# DS18B20.net
KiCad netlist of a schematic drawn in Altium Designer
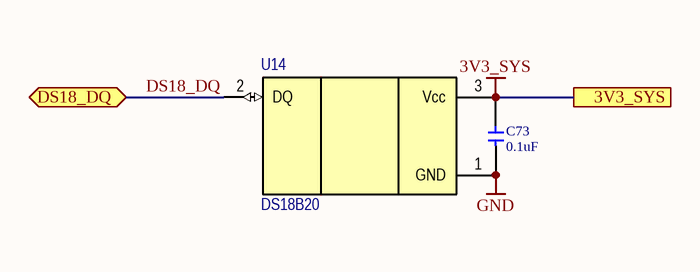
[diagram p0: DS18B20.SchDoc]

(export (version "E")
  (design (tool "Eeschema 10.0.6"))
  (components
    (comp (ref "C73")
      (value "0.1uF")
      (footprint "CERCAP 0603")
      (description "Capacitor")
      (fields (field (name "Comment") "CERCAP 0603 0.1uF * X7R"))
      (libsource (lib "!main") (part "!Capacitor"))
    )
    (comp (ref "U14")
      (value "DS18B20")
      (footprint "TO-92")
      (description "Temp")
      (libsource (lib "sensors") (part "DS18B20"))
    )
  )
  (nets
    (net (code "1") (name "/DS18_DQ") (class "Default")
      (node (ref "U14") (pin "2") (pinfunction "DQ_2") (pintype "bidirectional"))
    )
    (net (code "2") (name "3V3_SYS") (class "Default")
      (node (ref "C73") (pin "2") (pintype "passive"))
      (node (ref "U14") (pin "3") (pinfunction "Vcc_3") (pintype "power_in"))
    )
    (net (code "3") (name "GND") (class "Default")
      (node (ref "C73") (pin "1") (pintype "passive"))
      (node (ref "U14") (pin "1") (pinfunction "GND_1") (pintype "power_in"))
    )
  )
)
